# led-controller.net
KiCad netlist of a schematic drawn in EAGLE
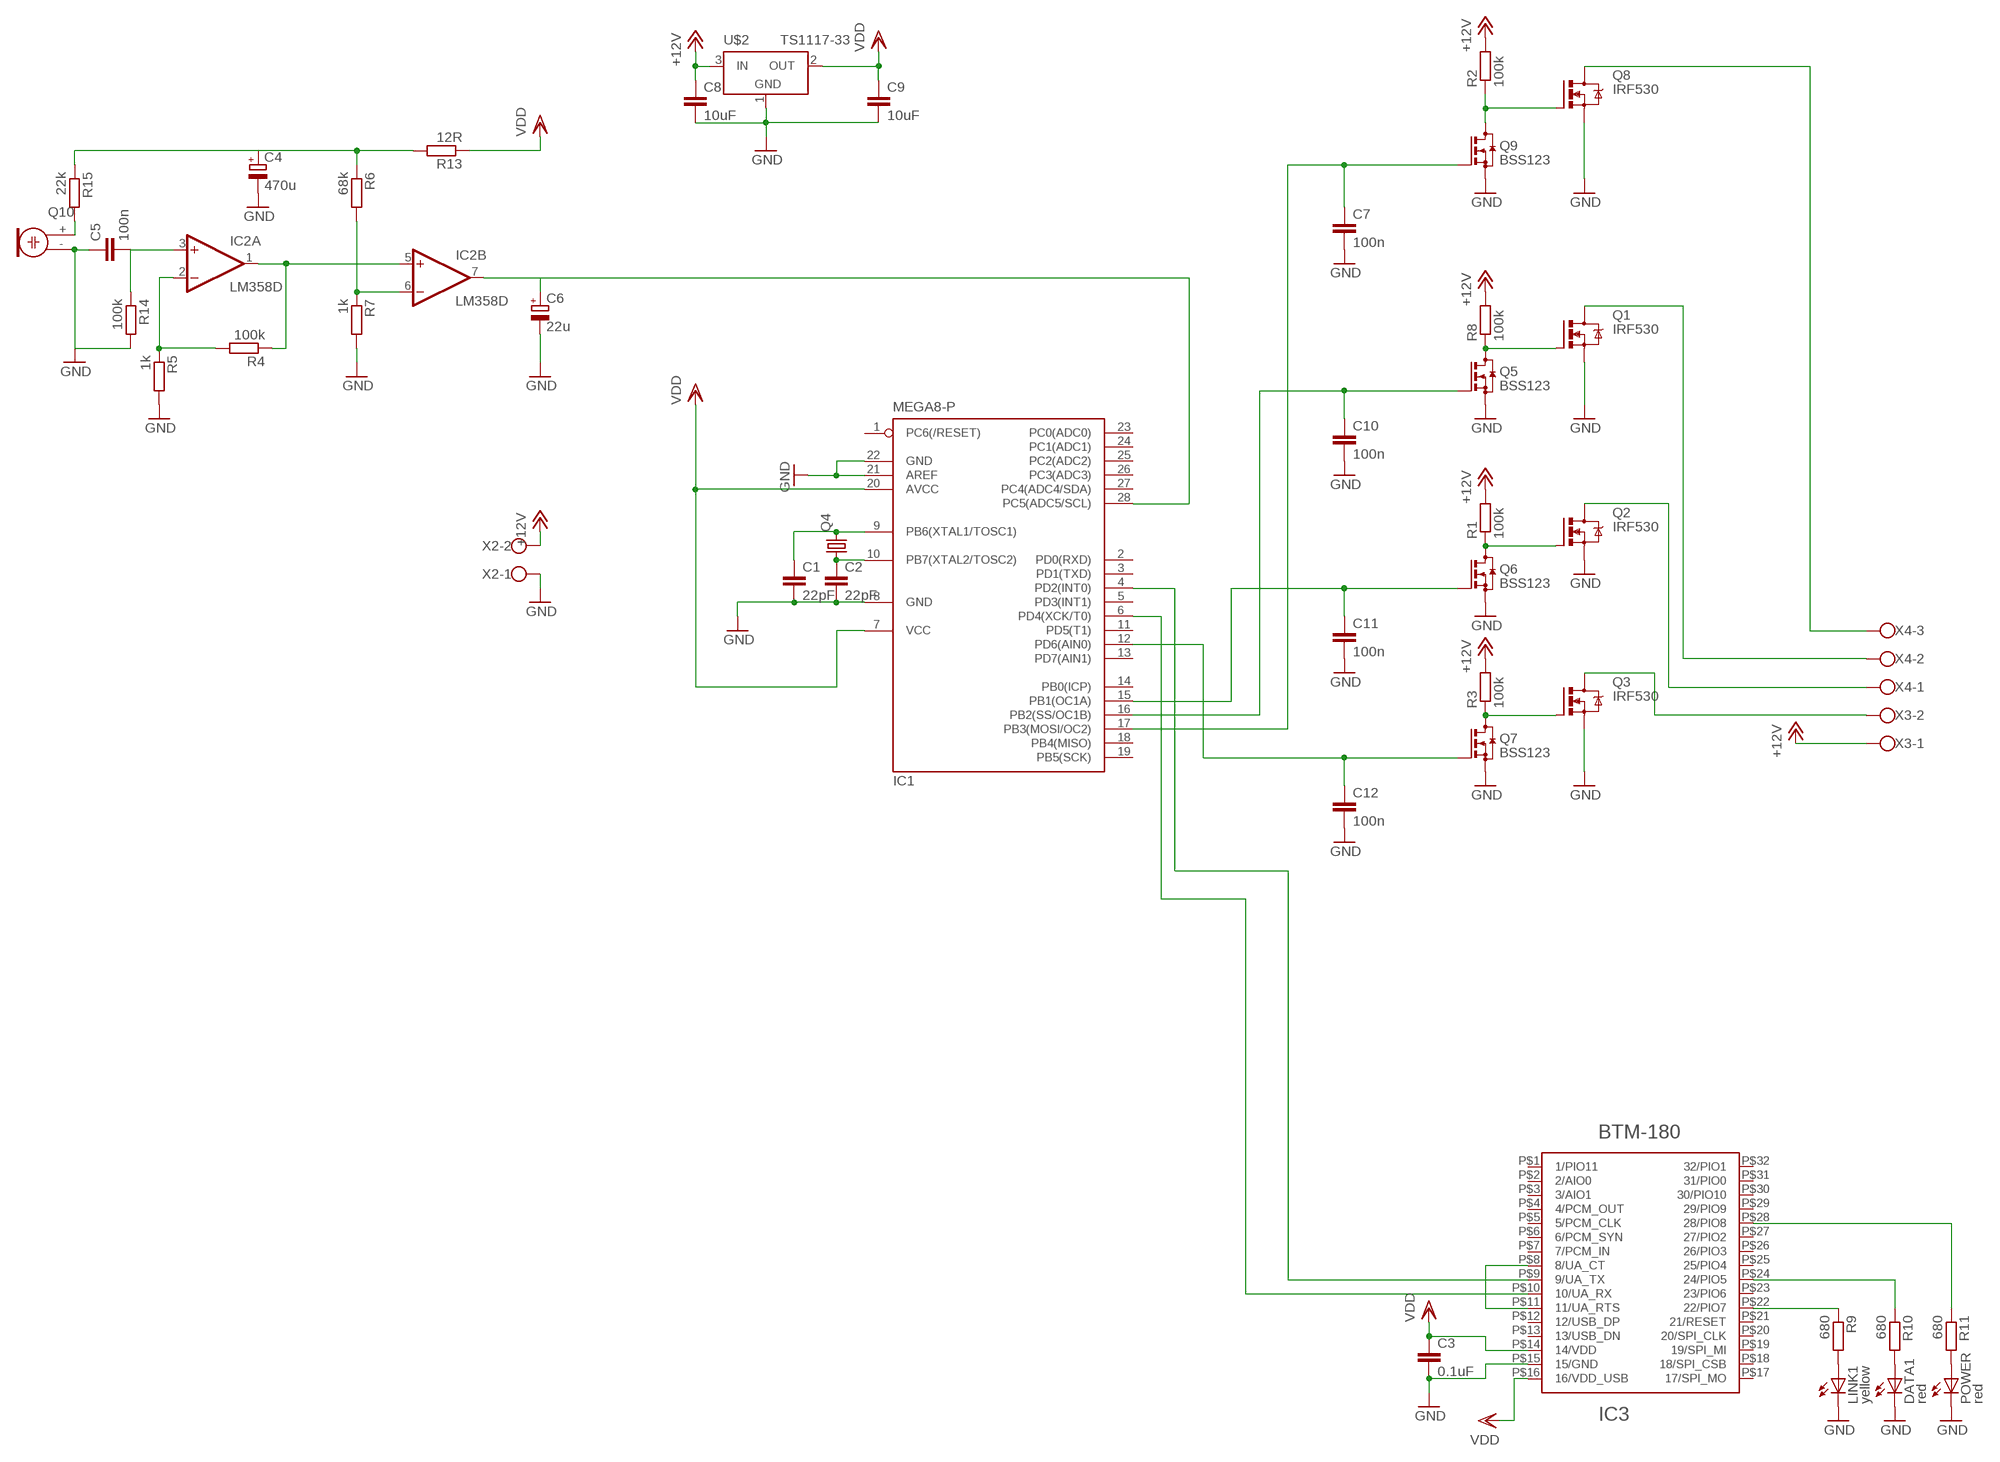
[diagram p0: schematic, sheet 1]

(export (version "E")
  (design (tool "Eeschema 10.0.6"))
  (components
    (comp (ref "C1")
      (value "22pF")
      (footprint "eagle-import:C0805K")
      (libsource (lib "eagle-import") (part "C-EUC0805K"))
    )
    (comp (ref "C2")
      (value "22pF")
      (footprint "eagle-import:C0805K")
      (libsource (lib "eagle-import") (part "C-EUC0805K"))
    )
    (comp (ref "C3")
      (value "0.1uF")
      (footprint "eagle-import:C0805K")
      (libsource (lib "eagle-import") (part "C-EUC0805K"))
    )
    (comp (ref "C4")
      (value "470u")
      (footprint "eagle-import:E2-4")
      (libsource (lib "eagle-import") (part "CPOL-EUE2-4"))
    )
    (comp (ref "C5")
      (value "100n")
      (footprint "eagle-import:C0805K")
      (libsource (lib "eagle-import") (part "C-EUC0805K"))
    )
    (comp (ref "C6")
      (value "22u")
      (footprint "eagle-import:E2-4")
      (libsource (lib "eagle-import") (part "CPOL-EUE2-4"))
    )
    (comp (ref "C7")
      (value "100n")
      (footprint "eagle-import:C0805K")
      (libsource (lib "eagle-import") (part "C-EUC0805K"))
    )
    (comp (ref "C8")
      (value "10uF")
      (footprint "eagle-import:C1206K")
      (libsource (lib "eagle-import") (part "C-EUC1206K"))
    )
    (comp (ref "C9")
      (value "10uF")
      (footprint "eagle-import:C1206K")
      (libsource (lib "eagle-import") (part "C-EUC1206K"))
    )
    (comp (ref "C10")
      (value "100n")
      (footprint "eagle-import:C0805K")
      (libsource (lib "eagle-import") (part "C-EUC0805K"))
    )
    (comp (ref "C11")
      (value "100n")
      (footprint "eagle-import:C0805K")
      (libsource (lib "eagle-import") (part "C-EUC0805K"))
    )
    (comp (ref "C12")
      (value "100n")
      (footprint "eagle-import:C0805K")
      (libsource (lib "eagle-import") (part "C-EUC0805K"))
    )
    (comp (ref "DATA1")
      (value "red")
      (footprint "eagle-import:CHIPLED_0603")
      (fields (field (name "MF") "AIM-TTI INSTRUMENTS") (field (name "MPN") "037107"))
      (libsource (lib "eagle-import") (part "LEDCHIPLED_0603"))
    )
    (comp (ref "IC1")
      (value "MEGA8-P")
      (footprint "eagle-import:DIL28-3")
      (libsource (lib "eagle-import") (part "MEGA8-P"))
    )
    (comp (ref "IC2")
      (value "LM358D")
      (footprint "eagle-import:SO08")
      (libsource (lib "eagle-import") (part "LM358D"))
    )
    (comp (ref "IC3")
      (value "BTM-180")
      (footprint "eagle-import:BTM-180")
      (libsource (lib "eagle-import") (part "BTM-180"))
    )
    (comp (ref "LINK1")
      (value "yellow")
      (footprint "eagle-import:CHIPLED_0603")
      (libsource (lib "eagle-import") (part "LEDCHIPLED_0603"))
    )
    (comp (ref "POWER")
      (value "red")
      (footprint "eagle-import:CHIPLED_0603")
      (libsource (lib "eagle-import") (part "LEDCHIPLED_0603"))
    )
    (comp (ref "Q1")
      (value "IRF530")
      (footprint "eagle-import:TO220BV")
      (libsource (lib "eagle-import") (part "IRF530"))
    )
    (comp (ref "Q2")
      (value "IRF530")
      (footprint "eagle-import:TO220BV")
      (libsource (lib "eagle-import") (part "IRF530"))
    )
    (comp (ref "Q3")
      (value "IRF530")
      (footprint "eagle-import:TO220BV")
      (libsource (lib "eagle-import") (part "IRF530"))
    )
    (comp (ref "Q4")
      (value "CRYSTALHC49S")
      (footprint "eagle-import:HC49_S")
      (libsource (lib "eagle-import") (part "CRYSTALHC49S"))
    )
    (comp (ref "Q5")
      (value "BSS123")
      (footprint "eagle-import:SOT23")
      (libsource (lib "eagle-import") (part "BSS123"))
    )
    (comp (ref "Q6")
      (value "BSS123")
      (footprint "eagle-import:SOT23")
      (libsource (lib "eagle-import") (part "BSS123"))
    )
    (comp (ref "Q7")
      (value "BSS123")
      (footprint "eagle-import:SOT23")
      (libsource (lib "eagle-import") (part "BSS123"))
    )
    (comp (ref "Q8")
      (value "IRF530")
      (footprint "eagle-import:TO220BV")
      (libsource (lib "eagle-import") (part "IRF530"))
    )
    (comp (ref "Q9")
      (value "BSS123")
      (footprint "eagle-import:SOT23")
      (libsource (lib "eagle-import") (part "BSS123"))
    )
    (comp (ref "Q10")
      (value "ELECTRET")
      (footprint "eagle-import:9.7ELECTRET")
      (libsource (lib "eagle-import") (part "ELECTRET"))
    )
    (comp (ref "R1")
      (value "100k")
      (footprint "eagle-import:R0603")
      (libsource (lib "eagle-import") (part "R-EU_R0603"))
    )
    (comp (ref "R2")
      (value "100k")
      (footprint "eagle-import:R0603")
      (libsource (lib "eagle-import") (part "R-EU_R0603"))
    )
    (comp (ref "R3")
      (value "100k")
      (footprint "eagle-import:R0603")
      (libsource (lib "eagle-import") (part "R-EU_R0603"))
    )
    (comp (ref "R4")
      (value "100k")
      (footprint "eagle-import:R0603")
      (libsource (lib "eagle-import") (part "R-EU_R0603"))
    )
    (comp (ref "R5")
      (value "1k")
      (footprint "eagle-import:R0603")
      (libsource (lib "eagle-import") (part "R-EU_R0603"))
    )
    (comp (ref "R6")
      (value "68k")
      (footprint "eagle-import:R0603")
      (libsource (lib "eagle-import") (part "R-EU_R0603"))
    )
    (comp (ref "R7")
      (value "1k")
      (footprint "eagle-import:R0603")
      (libsource (lib "eagle-import") (part "R-EU_R0603"))
    )
    (comp (ref "R8")
      (value "100k")
      (footprint "eagle-import:R0603")
      (libsource (lib "eagle-import") (part "R-EU_R0603"))
    )
    (comp (ref "R9")
      (value "680")
      (footprint "eagle-import:R0603")
      (libsource (lib "eagle-import") (part "R-EU_R0603"))
    )
    (comp (ref "R10")
      (value "680")
      (footprint "eagle-import:R0603")
      (libsource (lib "eagle-import") (part "R-EU_R0603"))
    )
    (comp (ref "R11")
      (value "680")
      (footprint "eagle-import:R0603")
      (libsource (lib "eagle-import") (part "R-EU_R0603"))
    )
    (comp (ref "R13")
      (value "12R")
      (footprint "eagle-import:R0603")
      (libsource (lib "eagle-import") (part "R-EU_R0603"))
    )
    (comp (ref "R14")
      (value "100k")
      (footprint "eagle-import:R0603")
      (libsource (lib "eagle-import") (part "R-EU_R0603"))
    )
    (comp (ref "R15")
      (value "22k")
      (footprint "eagle-import:R0603")
      (libsource (lib "eagle-import") (part "R-EU_R0603"))
    )
    (comp (ref "U$2")
      (value "TS1117-33")
      (footprint "eagle-import:TO220")
      (libsource (lib "eagle-import") (part "TS1117-TO220"))
    )
    (comp (ref "X2")
      (value "W237-102")
      (footprint "eagle-import:W237-102")
      (fields (field (name "MPN") "237-102"))
      (libsource (lib "eagle-import") (part "W237-102"))
    )
    (comp (ref "X3")
      (value "W237-102")
      (footprint "eagle-import:W237-102")
      (fields (field (name "MPN") "237-102"))
      (libsource (lib "eagle-import") (part "W237-102"))
    )
    (comp (ref "X4")
      (value "W237-103")
      (footprint "eagle-import:W237-103")
      (fields (field (name "MPN") "237-103"))
      (libsource (lib "eagle-import") (part "W237-103"))
    )
  )
  (nets
    (net (code "1") (name "+12V") (class "Default")
      (node (ref "C8") (pin "1") (pinfunction "1_1") (pintype "passive"))
      (node (ref "R1") (pin "2") (pinfunction "2_2") (pintype "passive"))
      (node (ref "R2") (pin "2") (pinfunction "2_2") (pintype "passive"))
      (node (ref "R3") (pin "2") (pinfunction "2_2") (pintype "passive"))
      (node (ref "R8") (pin "2") (pinfunction "2_2") (pintype "passive"))
      (node (ref "U$2") (pin "3") (pinfunction "IN_3") (pintype "input"))
      (node (ref "X2") (pin "2") (pinfunction "KL_2") (pintype "passive"))
      (node (ref "X3") (pin "1") (pinfunction "KL_1") (pintype "passive"))
    )
    (net (code "2") (name "/N$20") (class "Default")
      (node (ref "IC3") (pin "P$11") (pinfunction "11/UA_RTS_P$11") (pintype "output"))
      (node (ref "IC3") (pin "P$8") (pinfunction "8/UA_CT_P$8") (pintype "input"))
    )
    (net (code "3") (name "GND") (class "Default")
      (node (ref "C1") (pin "2") (pinfunction "2_2") (pintype "passive"))
      (node (ref "C10") (pin "2") (pinfunction "2_2") (pintype "passive"))
      (node (ref "C11") (pin "2") (pinfunction "2_2") (pintype "passive"))
      (node (ref "C12") (pin "2") (pinfunction "2_2") (pintype "passive"))
      (node (ref "C2") (pin "2") (pinfunction "2_2") (pintype "passive"))
      (node (ref "C3") (pin "2") (pinfunction "2_2") (pintype "passive"))
      (node (ref "C4") (pin "-") (pinfunction "-_-") (pintype "passive"))
      (node (ref "C5") (pin "1") (pinfunction "1_1") (pintype "passive"))
      (node (ref "C6") (pin "-") (pinfunction "-_-") (pintype "passive"))
      (node (ref "C7") (pin "2") (pinfunction "2_2") (pintype "passive"))
      (node (ref "C8") (pin "2") (pinfunction "2_2") (pintype "passive"))
      (node (ref "C9") (pin "2") (pinfunction "2_2") (pintype "passive"))
      (node (ref "DATA1") (pin "C") (pinfunction "C_C") (pintype "passive"))
      (node (ref "IC1") (pin "21") (pinfunction "AREF_21") (pintype "passive"))
      (node (ref "IC1") (pin "22") (pinfunction "GND_22") (pintype "power_in"))
      (node (ref "IC1") (pin "8") (pinfunction "GND_8") (pintype "power_in"))
      (node (ref "IC3") (pin "P$15") (pinfunction "15/GND_P$15") (pintype "power_in"))
      (node (ref "LINK1") (pin "C") (pinfunction "C_C") (pintype "passive"))
      (node (ref "POWER") (pin "C") (pinfunction "C_C") (pintype "passive"))
      (node (ref "Q1") (pin "S") (pinfunction "S_S") (pintype "passive"))
      (node (ref "Q10") (pin "-") (pinfunction "1_-") (pintype "passive"))
      (node (ref "Q2") (pin "S") (pinfunction "S_S") (pintype "passive"))
      (node (ref "Q3") (pin "S") (pinfunction "S_S") (pintype "passive"))
      (node (ref "Q5") (pin "2") (pinfunction "S_2") (pintype "passive"))
      (node (ref "Q6") (pin "2") (pinfunction "S_2") (pintype "passive"))
      (node (ref "Q7") (pin "2") (pinfunction "S_2") (pintype "passive"))
      (node (ref "Q8") (pin "S") (pinfunction "S_S") (pintype "passive"))
      (node (ref "Q9") (pin "2") (pinfunction "S_2") (pintype "passive"))
      (node (ref "R14") (pin "2") (pinfunction "2_2") (pintype "passive"))
      (node (ref "R5") (pin "2") (pinfunction "2_2") (pintype "passive"))
      (node (ref "R7") (pin "2") (pinfunction "2_2") (pintype "passive"))
      (node (ref "U$2") (pin "1") (pinfunction "GND_1") (pintype "power_in"))
      (node (ref "X2") (pin "1") (pinfunction "KL_1") (pintype "passive"))
    )
    (net (code "4") (name "Net-(C4-Pad+)") (class "Default")
      (node (ref "C4") (pin "+") (pinfunction "+_+") (pintype "passive"))
      (node (ref "R13") (pin "2") (pinfunction "2_2") (pintype "passive"))
      (node (ref "R15") (pin "1") (pinfunction "1_1") (pintype "passive"))
      (node (ref "R6") (pin "1") (pinfunction "1_1") (pintype "passive"))
    )
    (net (code "5") (name "Net-(DATA1-PadA)") (class "Default")
      (node (ref "DATA1") (pin "A") (pinfunction "A_A") (pintype "passive"))
      (node (ref "R10") (pin "2") (pinfunction "2_2") (pintype "passive"))
    )
    (net (code "6") (name "Net-(IC1-PB1(OC1A))") (class "Default")
      (node (ref "C11") (pin "1") (pinfunction "1_1") (pintype "passive"))
      (node (ref "IC1") (pin "15") (pinfunction "PB1(OC1A)_15") (pintype "bidirectional"))
      (node (ref "Q6") (pin "1") (pinfunction "G_1") (pintype "passive"))
    )
    (net (code "7") (name "Net-(IC1-PB2(SS{slash}OC1B))") (class "Default")
      (node (ref "C10") (pin "1") (pinfunction "1_1") (pintype "passive"))
      (node (ref "IC1") (pin "16") (pinfunction "PB2(SS/OC1B)_16") (pintype "bidirectional"))
      (node (ref "Q5") (pin "1") (pinfunction "G_1") (pintype "passive"))
    )
    (net (code "8") (name "Net-(IC1-PB3(MOSI{slash}OC2))") (class "Default")
      (node (ref "C7") (pin "1") (pinfunction "1_1") (pintype "passive"))
      (node (ref "IC1") (pin "17") (pinfunction "PB3(MOSI/OC2)_17") (pintype "bidirectional"))
      (node (ref "Q9") (pin "1") (pinfunction "G_1") (pintype "passive"))
    )
    (net (code "9") (name "Net-(IC1-PB6(XTAL1{slash}TOSC1))") (class "Default")
      (node (ref "C1") (pin "1") (pinfunction "1_1") (pintype "passive"))
      (node (ref "IC1") (pin "9") (pinfunction "PB6(XTAL1/TOSC1)_9") (pintype "bidirectional"))
      (node (ref "Q4") (pin "2") (pinfunction "2_2") (pintype "passive"))
    )
    (net (code "10") (name "Net-(IC1-PB7(XTAL2{slash}TOSC2))") (class "Default")
      (node (ref "C2") (pin "1") (pinfunction "1_1") (pintype "passive"))
      (node (ref "IC1") (pin "10") (pinfunction "PB7(XTAL2/TOSC2)_10") (pintype "bidirectional"))
      (node (ref "Q4") (pin "1") (pinfunction "1_1") (pintype "passive"))
    )
    (net (code "11") (name "Net-(IC1-PC5(ADC5{slash}SCL))") (class "Default")
      (node (ref "C6") (pin "+") (pinfunction "+_+") (pintype "passive"))
      (node (ref "IC1") (pin "28") (pinfunction "PC5(ADC5/SCL)_28") (pintype "bidirectional"))
      (node (ref "IC2") (pin "7") (pinfunction "OUT_7") (pintype "output"))
    )
    (net (code "12") (name "Net-(IC1-PD2(INT0))") (class "Default")
      (node (ref "IC1") (pin "4") (pinfunction "PD2(INT0)_4") (pintype "bidirectional"))
      (node (ref "IC3") (pin "P$9") (pinfunction "9/UA_TX_P$9") (pintype "output"))
    )
    (net (code "13") (name "Net-(IC1-PD4(XCK{slash}T0))") (class "Default")
      (node (ref "IC1") (pin "6") (pinfunction "PD4(XCK/T0)_6") (pintype "bidirectional"))
      (node (ref "IC3") (pin "P$10") (pinfunction "10/UA_RX_P$10") (pintype "input"))
    )
    (net (code "14") (name "Net-(IC1-PD6(AIN0))") (class "Default")
      (node (ref "C12") (pin "1") (pinfunction "1_1") (pintype "passive"))
      (node (ref "IC1") (pin "12") (pinfunction "PD6(AIN0)_12") (pintype "bidirectional"))
      (node (ref "Q7") (pin "1") (pinfunction "G_1") (pintype "passive"))
    )
    (net (code "15") (name "Net-(IC2A-+IN)") (class "Default")
      (node (ref "C5") (pin "2") (pinfunction "2_2") (pintype "passive"))
      (node (ref "IC2") (pin "3") (pinfunction "+IN_3") (pintype "input"))
      (node (ref "R14") (pin "1") (pinfunction "1_1") (pintype "passive"))
    )
    (net (code "16") (name "Net-(IC2A--IN)") (class "Default")
      (node (ref "IC2") (pin "2") (pinfunction "-IN_2") (pintype "input"))
      (node (ref "R4") (pin "2") (pinfunction "2_2") (pintype "passive"))
      (node (ref "R5") (pin "1") (pinfunction "1_1") (pintype "passive"))
    )
    (net (code "17") (name "Net-(IC2A-OUT)") (class "Default")
      (node (ref "IC2") (pin "1") (pinfunction "OUT_1") (pintype "output"))
      (node (ref "IC2") (pin "5") (pinfunction "+IN_5") (pintype "input"))
      (node (ref "R4") (pin "1") (pinfunction "1_1") (pintype "passive"))
    )
    (net (code "18") (name "Net-(IC2B--IN)") (class "Default")
      (node (ref "IC2") (pin "6") (pinfunction "-IN_6") (pintype "input"))
      (node (ref "R6") (pin "2") (pinfunction "2_2") (pintype "passive"))
      (node (ref "R7") (pin "1") (pinfunction "1_1") (pintype "passive"))
    )
    (net (code "19") (name "Net-(IC3-22{slash}PIO7)") (class "Default")
      (node (ref "IC3") (pin "P$22") (pinfunction "22/PIO7_P$22") (pintype "bidirectional"))
      (node (ref "R9") (pin "1") (pinfunction "1_1") (pintype "passive"))
    )
    (net (code "20") (name "Net-(IC3-24{slash}PIO5)") (class "Default")
      (node (ref "IC3") (pin "P$24") (pinfunction "24/PIO5_P$24") (pintype "bidirectional"))
      (node (ref "R10") (pin "1") (pinfunction "1_1") (pintype "passive"))
    )
    (net (code "21") (name "Net-(IC3-28{slash}PIO8)") (class "Default")
      (node (ref "IC3") (pin "P$28") (pinfunction "28/PIO8_P$28") (pintype "bidirectional"))
      (node (ref "R11") (pin "1") (pinfunction "1_1") (pintype "passive"))
    )
    (net (code "22") (name "Net-(LINK1-PadA)") (class "Default")
      (node (ref "LINK1") (pin "A") (pinfunction "A_A") (pintype "passive"))
      (node (ref "R9") (pin "2") (pinfunction "2_2") (pintype "passive"))
    )
    (net (code "23") (name "Net-(POWER-PadA)") (class "Default")
      (node (ref "POWER") (pin "A") (pinfunction "A_A") (pintype "passive"))
      (node (ref "R11") (pin "2") (pinfunction "2_2") (pintype "passive"))
    )
    (net (code "24") (name "Net-(Q5-D)") (class "Default")
      (node (ref "Q1") (pin "G") (pinfunction "G_G") (pintype "passive"))
      (node (ref "Q5") (pin "3") (pinfunction "D_3") (pintype "passive"))
      (node (ref "R8") (pin "1") (pinfunction "1_1") (pintype "passive"))
    )
    (net (code "25") (name "Net-(Q6-D)") (class "Default")
      (node (ref "Q2") (pin "G") (pinfunction "G_G") (pintype "passive"))
      (node (ref "Q6") (pin "3") (pinfunction "D_3") (pintype "passive"))
      (node (ref "R1") (pin "1") (pinfunction "1_1") (pintype "passive"))
    )
    (net (code "26") (name "Net-(Q7-D)") (class "Default")
      (node (ref "Q3") (pin "G") (pinfunction "G_G") (pintype "passive"))
      (node (ref "Q7") (pin "3") (pinfunction "D_3") (pintype "passive"))
      (node (ref "R3") (pin "1") (pinfunction "1_1") (pintype "passive"))
    )
    (net (code "27") (name "Net-(Q9-D)") (class "Default")
      (node (ref "Q8") (pin "G") (pinfunction "G_G") (pintype "passive"))
      (node (ref "Q9") (pin "3") (pinfunction "D_3") (pintype "passive"))
      (node (ref "R2") (pin "1") (pinfunction "1_1") (pintype "passive"))
    )
    (net (code "28") (name "Net-(Q10-2)") (class "Default")
      (node (ref "Q10") (pin "+") (pinfunction "2_+") (pintype "passive"))
      (node (ref "R15") (pin "2") (pinfunction "2_2") (pintype "passive"))
    )
    (net (code "29") (name "Net-(X3B-KL)") (class "Default")
      (node (ref "Q3") (pin "D") (pinfunction "D_D") (pintype "passive"))
      (node (ref "X3") (pin "2") (pinfunction "KL_2") (pintype "passive"))
    )
    (net (code "30") (name "Net-(X4A-KL)") (class "Default")
      (node (ref "Q2") (pin "D") (pinfunction "D_D") (pintype "passive"))
      (node (ref "X4") (pin "1") (pinfunction "KL_1") (pintype "passive"))
    )
    (net (code "31") (name "Net-(X4B-KL)") (class "Default")
      (node (ref "Q1") (pin "D") (pinfunction "D_D") (pintype "passive"))
      (node (ref "X4") (pin "2") (pinfunction "KL_2") (pintype "passive"))
    )
    (net (code "32") (name "Net-(X4C-KL)") (class "Default")
      (node (ref "Q8") (pin "D") (pinfunction "D_D") (pintype "passive"))
      (node (ref "X4") (pin "3") (pinfunction "KL_3") (pintype "passive"))
    )
    (net (code "33") (name "VDD") (class "Default")
      (node (ref "C3") (pin "1") (pinfunction "1_1") (pintype "passive"))
      (node (ref "C9") (pin "1") (pinfunction "1_1") (pintype "passive"))
      (node (ref "IC1") (pin "20") (pinfunction "AVCC_20") (pintype "power_in"))
      (node (ref "IC1") (pin "7") (pinfunction "VCC_7") (pintype "power_in"))
      (node (ref "IC3") (pin "P$14") (pinfunction "14/VDD_P$14") (pintype "power_in"))
      (node (ref "IC3") (pin "P$16") (pinfunction "16/VDD_USB_P$16") (pintype "power_in"))
      (node (ref "R13") (pin "1") (pinfunction "1_1") (pintype "passive"))
      (node (ref "U$2") (pin "2") (pinfunction "OUT_2") (pintype "output"))
    )
    (net (code "34") (name "unconnected-(IC1-PB0(ICP)-Pad14)") (class "Default")
      (node (ref "IC1") (pin "14") (pinfunction "PB0(ICP)_14") (pintype "bidirectional"))
    )
    (net (code "35") (name "unconnected-(IC1-PB4(MISO)-Pad18)") (class "Default")
      (node (ref "IC1") (pin "18") (pinfunction "PB4(MISO)_18") (pintype "bidirectional"))
    )
    (net (code "36") (name "unconnected-(IC1-PB5(SCK)-Pad19)") (class "Default")
      (node (ref "IC1") (pin "19") (pinfunction "PB5(SCK)_19") (pintype "bidirectional"))
    )
    (net (code "37") (name "unconnected-(IC1-PC0(ADC0)-Pad23)") (class "Default")
      (node (ref "IC1") (pin "23") (pinfunction "PC0(ADC0)_23") (pintype "bidirectional"))
    )
    (net (code "38") (name "unconnected-(IC1-PC1(ADC1)-Pad24)") (class "Default")
      (node (ref "IC1") (pin "24") (pinfunction "PC1(ADC1)_24") (pintype "bidirectional"))
    )
    (net (code "39") (name "unconnected-(IC1-PC2(ADC2)-Pad25)") (class "Default")
      (node (ref "IC1") (pin "25") (pinfunction "PC2(ADC2)_25") (pintype "bidirectional"))
    )
    (net (code "40") (name "unconnected-(IC1-PC3(ADC3)-Pad26)") (class "Default")
      (node (ref "IC1") (pin "26") (pinfunction "PC3(ADC3)_26") (pintype "bidirectional"))
    )
    (net (code "41") (name "unconnected-(IC1-PC4(ADC4{slash}SDA)-Pad27)") (class "Default")
      (node (ref "IC1") (pin "27") (pinfunction "PC4(ADC4/SDA)_27") (pintype "bidirectional"))
    )
    (net (code "42") (name "unconnected-(IC1-PC6({slash}RESET)-Pad1)") (class "Default")
      (node (ref "IC1") (pin "1") (pinfunction "PC6(/RESET)_1") (pintype "bidirectional"))
    )
    (net (code "43") (name "unconnected-(IC1-PD0(RXD)-Pad2)") (class "Default")
      (node (ref "IC1") (pin "2") (pinfunction "PD0(RXD)_2") (pintype "bidirectional"))
    )
    (net (code "44") (name "unconnected-(IC1-PD1(TXD)-Pad3)") (class "Default")
      (node (ref "IC1") (pin "3") (pinfunction "PD1(TXD)_3") (pintype "bidirectional"))
    )
    (net (code "45") (name "unconnected-(IC1-PD3(INT1)-Pad5)") (class "Default")
      (node (ref "IC1") (pin "5") (pinfunction "PD3(INT1)_5") (pintype "bidirectional"))
    )
    (net (code "46") (name "unconnected-(IC1-PD5(T1)-Pad11)") (class "Default")
      (node (ref "IC1") (pin "11") (pinfunction "PD5(T1)_11") (pintype "bidirectional"))
    )
    (net (code "47") (name "unconnected-(IC1-PD7(AIN1)-Pad13)") (class "Default")
      (node (ref "IC1") (pin "13") (pinfunction "PD7(AIN1)_13") (pintype "bidirectional"))
    )
    (net (code "48") (name "unconnected-(IC3-1{slash}PIO11-PadP$1)") (class "Default")
      (node (ref "IC3") (pin "P$1") (pinfunction "1/PIO11_P$1") (pintype "bidirectional"))
    )
    (net (code "49") (name "unconnected-(IC3-2{slash}AIO0-PadP$2)") (class "Default")
      (node (ref "IC3") (pin "P$2") (pinfunction "2/AIO0_P$2") (pintype "bidirectional"))
    )
    (net (code "50") (name "unconnected-(IC3-3{slash}AIO1-PadP$3)") (class "Default")
      (node (ref "IC3") (pin "P$3") (pinfunction "3/AIO1_P$3") (pintype "bidirectional"))
    )
    (net (code "51") (name "unconnected-(IC3-4{slash}PCM_OUT-PadP$4)") (class "Default")
      (node (ref "IC3") (pin "P$4") (pinfunction "4/PCM_OUT_P$4") (pintype "output"))
    )
    (net (code "52") (name "unconnected-(IC3-5{slash}PCM_CLK-PadP$5)") (class "Default")
      (node (ref "IC3") (pin "P$5") (pinfunction "5/PCM_CLK_P$5") (pintype "bidirectional"))
    )
    (net (code "53") (name "unconnected-(IC3-6{slash}PCM_SYN-PadP$6)") (class "Default")
      (node (ref "IC3") (pin "P$6") (pinfunction "6/PCM_SYN_P$6") (pintype "input"))
    )
    (net (code "54") (name "unconnected-(IC3-7{slash}PCM_IN-PadP$7)") (class "Default")
      (node (ref "IC3") (pin "P$7") (pinfunction "7/PCM_IN_P$7") (pintype "input"))
    )
    (net (code "55") (name "unconnected-(IC3-12{slash}USB_DP-PadP$12)") (class "Default")
      (node (ref "IC3") (pin "P$12") (pinfunction "12/USB_DP_P$12") (pintype "bidirectional"))
    )
    (net (code "56") (name "unconnected-(IC3-13{slash}USB_DN-PadP$13)") (class "Default")
      (node (ref "IC3") (pin "P$13") (pinfunction "13/USB_DN_P$13") (pintype "bidirectional"))
    )
    (net (code "57") (name "unconnected-(IC3-17{slash}SPI_MO-PadP$17)") (class "Default")
      (node (ref "IC3") (pin "P$17") (pinfunction "17/SPI_MO_P$17") (pintype "input"))
    )
    (net (code "58") (name "unconnected-(IC3-18{slash}SPI_CSB-PadP$18)") (class "Default")
      (node (ref "IC3") (pin "P$18") (pinfunction "18/SPI_CSB_P$18") (pintype "input"))
    )
    (net (code "59") (name "unconnected-(IC3-19{slash}SPI_MI-PadP$19)") (class "Default")
      (node (ref "IC3") (pin "P$19") (pinfunction "19/SPI_MI_P$19") (pintype "output"))
    )
    (net (code "60") (name "unconnected-(IC3-20{slash}SPI_CLK-PadP$20)") (class "Default")
      (node (ref "IC3") (pin "P$20") (pinfunction "20/SPI_CLK_P$20") (pintype "input"))
    )
    (net (code "61") (name "unconnected-(IC3-21{slash}RESET-PadP$21)") (class "Default")
      (node (ref "IC3") (pin "P$21") (pinfunction "21/RESET_P$21") (pintype "input"))
    )
    (net (code "62") (name "unconnected-(IC3-23{slash}PIO6-PadP$23)") (class "Default")
      (node (ref "IC3") (pin "P$23") (pinfunction "23/PIO6_P$23") (pintype "bidirectional"))
    )
    (net (code "63") (name "unconnected-(IC3-25{slash}PIO4-PadP$25)") (class "Default")
      (node (ref "IC3") (pin "P$25") (pinfunction "25/PIO4_P$25") (pintype "bidirectional"))
    )
    (net (code "64") (name "unconnected-(IC3-26{slash}PIO3-PadP$26)") (class "Default")
      (node (ref "IC3") (pin "P$26") (pinfunction "26/PIO3_P$26") (pintype "bidirectional"))
    )
    (net (code "65") (name "unconnected-(IC3-27{slash}PIO2-PadP$27)") (class "Default")
      (node (ref "IC3") (pin "P$27") (pinfunction "27/PIO2_P$27") (pintype "bidirectional"))
    )
    (net (code "66") (name "unconnected-(IC3-29{slash}PIO9-PadP$29)") (class "Default")
      (node (ref "IC3") (pin "P$29") (pinfunction "29/PIO9_P$29") (pintype "bidirectional"))
    )
    (net (code "67") (name "unconnected-(IC3-30{slash}PIO10-PadP$30)") (class "Default")
      (node (ref "IC3") (pin "P$30") (pinfunction "30/PIO10_P$30") (pintype "bidirectional"))
    )
    (net (code "68") (name "unconnected-(IC3-31{slash}PIO0-PadP$31)") (class "Default")
      (node (ref "IC3") (pin "P$31") (pinfunction "31/PIO0_P$31") (pintype "bidirectional"))
    )
    (net (code "69") (name "unconnected-(IC3-32{slash}PIO1-PadP$32)") (class "Default")
      (node (ref "IC3") (pin "P$32") (pinfunction "32/PIO1_P$32") (pintype "bidirectional"))
    )
  )
)
